# LiPolySonicScrewdriver.net
KiCad netlist of a schematic drawn in EAGLE
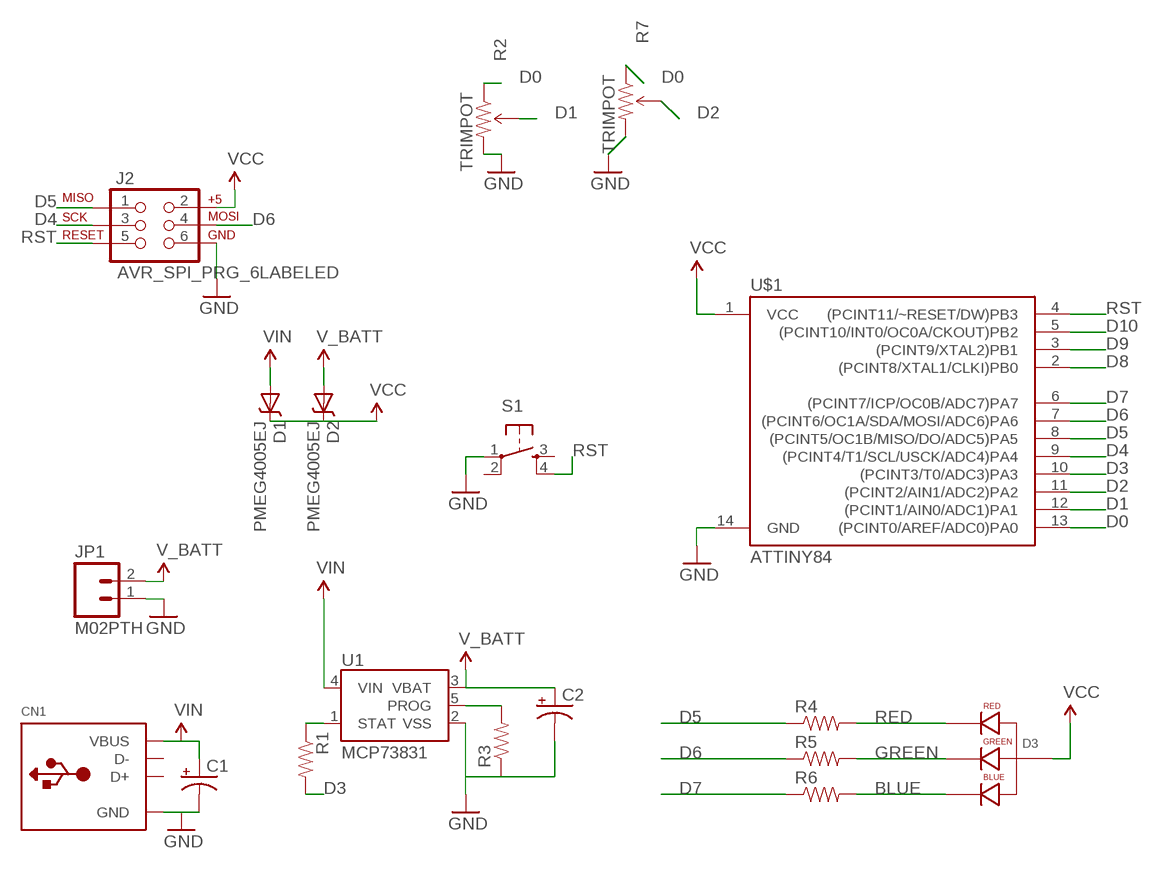
[diagram p0: schematic, sheet 1]

(export (version "E")
  (design (tool "Eeschema 10.0.6"))
  (components
    (comp (ref "C1")
      (value "CAP_POL1206")
      (footprint "eagle-import:EIA3216")
      (libsource (lib "eagle-import") (part "CAP_POL1206"))
    )
    (comp (ref "C2")
      (value "CAP_POL1206")
      (footprint "eagle-import:EIA3216")
      (libsource (lib "eagle-import") (part "CAP_POL1206"))
    )
    (comp (ref "CN1")
      (value "USB_TYPEAPCB")
      (footprint "eagle-import:USBA_PCB")
      (libsource (lib "eagle-import") (part "USB_TYPEAPCB"))
    )
    (comp (ref "D1")
      (value "PMEG4005EJ")
      (footprint "eagle-import:SOD-323")
      (libsource (lib "eagle-import") (part "DIODE-SCHOTTKY-PMEG4005EJ"))
    )
    (comp (ref "D2")
      (value "PMEG4005EJ")
      (footprint "eagle-import:SOD-323")
      (libsource (lib "eagle-import") (part "DIODE-SCHOTTKY-PMEG4005EJ"))
    )
    (comp (ref "D3")
      (value "LED-RGB-CA-THRUEDGE")
      (footprint "eagle-import:LED-RGB-EDGE")
      (libsource (lib "eagle-import") (part "LED-RGB-CA-THRUEDGE"))
    )
    (comp (ref "J2")
      (value "AVR_SPI_PRG_6LABELED")
      (footprint "eagle-import:2X3-NS")
      (libsource (lib "eagle-import") (part "AVR_SPI_PRG_6LABELED"))
    )
    (comp (ref "JP1")
      (value "M02PTH")
      (footprint "eagle-import:1X02")
      (libsource (lib "eagle-import") (part "M02PTH"))
    )
    (comp (ref "R1")
      (value "RESISTOR0805-RES")
      (footprint "eagle-import:0805")
      (libsource (lib "eagle-import") (part "RESISTOR0805-RES"))
    )
    (comp (ref "R2")
      (value "TRIMPOT")
      (footprint "eagle-import:TRIMPOT-5MM-V2")
      (libsource (lib "eagle-import") (part "TRIMPOT"))
    )
    (comp (ref "R3")
      (value "RESISTOR0805-RES")
      (footprint "eagle-import:0805")
      (libsource (lib "eagle-import") (part "RESISTOR0805-RES"))
    )
    (comp (ref "R4")
      (value "RESISTOR1206")
      (footprint "eagle-import:1206")
      (libsource (lib "eagle-import") (part "RESISTOR1206"))
    )
    (comp (ref "R5")
      (value "RESISTOR1206")
      (footprint "eagle-import:1206")
      (libsource (lib "eagle-import") (part "RESISTOR1206"))
    )
    (comp (ref "R6")
      (value "RESISTOR1206")
      (footprint "eagle-import:1206")
      (libsource (lib "eagle-import") (part "RESISTOR1206"))
    )
    (comp (ref "R7")
      (value "TRIMPOT")
      (footprint "eagle-import:TRIMPOT-5MM-V2")
      (libsource (lib "eagle-import") (part "TRIMPOT"))
    )
    (comp (ref "S1")
      (value "TAC_SWITCHSMD")
      (footprint "eagle-import:TACTILE-SWITCH-SMD")
      (libsource (lib "eagle-import") (part "TAC_SWITCHSMD"))
    )
    (comp (ref "U$1")
      (value "ATTINY84")
      (footprint "eagle-import:SO14")
      (libsource (lib "eagle-import") (part "ATTINY84"))
    )
    (comp (ref "U1")
      (value "MCP73831")
      (footprint "eagle-import:SOT23-5")
      (libsource (lib "eagle-import") (part "MCP73831"))
    )
  )
  (nets
    (net (code "1") (name "/BLUE") (class "Default")
      (node (ref "D3") (pin "4") (pinfunction "BLUE_CATHODE_4") (pintype "bidirectional"))
      (node (ref "R6") (pin "2") (pinfunction "2_2") (pintype "passive"))
    )
    (net (code "2") (name "/D0") (class "Default")
      (node (ref "R2") (pin "A") (pinfunction "CCW_A") (pintype "passive"))
      (node (ref "R7") (pin "A") (pinfunction "CCW_A") (pintype "passive"))
      (node (ref "U$1") (pin "13") (pinfunction "(PCINT0/AREF/ADC0)PA0_13") (pintype "bidirectional"))
    )
    (net (code "3") (name "/D1") (class "Default")
      (node (ref "R2") (pin "B") (pinfunction "WIPER_B") (pintype "passive"))
      (node (ref "U$1") (pin "12") (pinfunction "(PCINT1/AIN0/ADC1)PA1_12") (pintype "bidirectional"))
    )
    (net (code "4") (name "/D2") (class "Default")
      (node (ref "R7") (pin "B") (pinfunction "WIPER_B") (pintype "passive"))
      (node (ref "U$1") (pin "11") (pinfunction "(PCINT2/AIN1/ADC2)PA2_11") (pintype "bidirectional"))
    )
    (net (code "5") (name "/D3") (class "Default")
      (node (ref "R1") (pin "2") (pinfunction "2_2") (pintype "passive"))
      (node (ref "U$1") (pin "10") (pinfunction "(PCINT3/T0/ADC3)PA3_10") (pintype "bidirectional"))
    )
    (net (code "6") (name "/D4") (class "Default")
      (node (ref "J2") (pin "3") (pinfunction "3_3") (pintype "passive"))
      (node (ref "U$1") (pin "9") (pinfunction "(PCINT4/T1/SCL/USCK/ADC4)PA4_9") (pintype "bidirectional"))
    )
    (net (code "7") (name "/D5") (class "Default")
      (node (ref "J2") (pin "1") (pinfunction "1_1") (pintype "passive"))
      (node (ref "R4") (pin "1") (pinfunction "1_1") (pintype "passive"))
      (node (ref "U$1") (pin "8") (pinfunction "(PCINT5/OC1B/MISO/DO/ADC5)PA5_8") (pintype "bidirectional"))
    )
    (net (code "8") (name "/D6") (class "Default")
      (node (ref "J2") (pin "4") (pinfunction "4_4") (pintype "passive"))
      (node (ref "R5") (pin "1") (pinfunction "1_1") (pintype "passive"))
      (node (ref "U$1") (pin "7") (pinfunction "(PCINT6/OC1A/SDA/MOSI/ADC6)PA6_7") (pintype "bidirectional"))
    )
    (net (code "9") (name "/D7") (class "Default")
      (node (ref "R6") (pin "1") (pinfunction "1_1") (pintype "passive"))
      (node (ref "U$1") (pin "6") (pinfunction "(PCINT7/ICP/OC0B/ADC7)PA7_6") (pintype "bidirectional"))
    )
    (net (code "10") (name "/D8") (class "Default")
      (node (ref "U$1") (pin "2") (pinfunction "(PCINT8/XTAL1/CLKI)PB0_2") (pintype "bidirectional"))
    )
    (net (code "11") (name "/D9") (class "Default")
      (node (ref "U$1") (pin "3") (pinfunction "(PCINT9/XTAL2)PB1_3") (pintype "bidirectional"))
    )
    (net (code "12") (name "/D10") (class "Default")
      (node (ref "U$1") (pin "5") (pinfunction "(PCINT10/INT0/OC0A/CKOUT)PB2_5") (pintype "bidirectional"))
    )
    (net (code "13") (name "/GREEN") (class "Default")
      (node (ref "D3") (pin "3") (pinfunction "GREEN_CATHODE_3") (pintype "bidirectional"))
      (node (ref "R5") (pin "2") (pinfunction "2_2") (pintype "passive"))
    )
    (net (code "14") (name "/RED") (class "Default")
      (node (ref "D3") (pin "1") (pinfunction "RED_CATHODE_1") (pintype "bidirectional"))
      (node (ref "R4") (pin "2") (pinfunction "2_2") (pintype "passive"))
    )
    (net (code "15") (name "/RST") (class "Default")
      (node (ref "J2") (pin "5") (pinfunction "5_5") (pintype "passive"))
      (node (ref "S1") (pin "4") (pinfunction "4_4") (pintype "passive"))
      (node (ref "U$1") (pin "4") (pinfunction "(PCINT11/~{RESET/DW})PB3_4") (pintype "bidirectional"))
    )
    (net (code "16") (name "GND") (class "Default")
      (node (ref "C1") (pin "C") (pinfunction "-_C") (pintype "passive"))
      (node (ref "C2") (pin "C") (pinfunction "-_C") (pintype "passive"))
      (node (ref "CN1") (pin "GND") (pinfunction "GND_GND") (pintype "power_in"))
      (node (ref "J2") (pin "6") (pinfunction "6_6") (pintype "passive"))
      (node (ref "JP1") (pin "1") (pinfunction "1_1") (pintype "passive"))
      (node (ref "R2") (pin "C") (pinfunction "CW_C") (pintype "passive"))
      (node (ref "R3") (pin "1") (pinfunction "1_1") (pintype "passive"))
      (node (ref "R7") (pin "C") (pinfunction "CW_C") (pintype "passive"))
      (node (ref "S1") (pin "1") (pinfunction "1_1") (pintype "passive"))
      (node (ref "U$1") (pin "14") (pinfunction "GND_14") (pintype "bidirectional"))
      (node (ref "U1") (pin "2") (pinfunction "VSS_2") (pintype "power_in"))
    )
    (net (code "17") (name "Net-(U1-PROG)") (class "Default")
      (node (ref "R3") (pin "2") (pinfunction "2_2") (pintype "passive"))
      (node (ref "U1") (pin "5") (pinfunction "PROG_5") (pintype "input"))
    )
    (net (code "18") (name "Net-(U1-STAT)") (class "Default")
      (node (ref "R1") (pin "1") (pinfunction "1_1") (pintype "passive"))
      (node (ref "U1") (pin "1") (pinfunction "STAT_1") (pintype "output"))
    )
    (net (code "19") (name "VCC") (class "Default")
      (node (ref "D1") (pin "C") (pinfunction "C_C") (pintype "passive"))
      (node (ref "D2") (pin "C") (pinfunction "C_C") (pintype "passive"))
      (node (ref "D3") (pin "2") (pinfunction "ANODE_2") (pintype "bidirectional"))
      (node (ref "J2") (pin "2") (pinfunction "2_2") (pintype "passive"))
      (node (ref "U$1") (pin "1") (pinfunction "VCC_1") (pintype "bidirectional"))
    )
    (net (code "20") (name "VIN") (class "Default")
      (node (ref "C1") (pin "A") (pinfunction "+_A") (pintype "passive"))
      (node (ref "CN1") (pin "VCC") (pinfunction "VBUS_VCC") (pintype "power_in"))
      (node (ref "D1") (pin "A") (pinfunction "A_A") (pintype "passive"))
      (node (ref "U1") (pin "4") (pinfunction "VIN_4") (pintype "power_in"))
    )
    (net (code "21") (name "V_BATT") (class "Default")
      (node (ref "C2") (pin "A") (pinfunction "+_A") (pintype "passive"))
      (node (ref "D2") (pin "A") (pinfunction "A_A") (pintype "passive"))
      (node (ref "JP1") (pin "2") (pinfunction "2_2") (pintype "passive"))
      (node (ref "U1") (pin "3") (pinfunction "VBAT_3") (pintype "power_in"))
    )
    (net (code "22") (name "unconnected-(CN1-D+-PadUSB_PLUS)") (class "Default")
      (node (ref "CN1") (pin "USB_PLUS") (pinfunction "D+_USB_PLUS") (pintype "bidirectional"))
    )
    (net (code "23") (name "unconnected-(CN1-D--PadUSB_NEG)") (class "Default")
      (node (ref "CN1") (pin "USB_NEG") (pinfunction "D-_USB_NEG") (pintype "bidirectional"))
    )
    (net (code "24") (name "unconnected-(S1-Pad2)") (class "Default")
      (node (ref "S1") (pin "2") (pinfunction "2_2") (pintype "passive"))
    )
    (net (code "25") (name "unconnected-(S1-Pad3)") (class "Default")
      (node (ref "S1") (pin "3") (pinfunction "3_3") (pintype "passive"))
    )
  )
)
